# power_on.net
KiCad netlist of a schematic drawn in Altium Designer
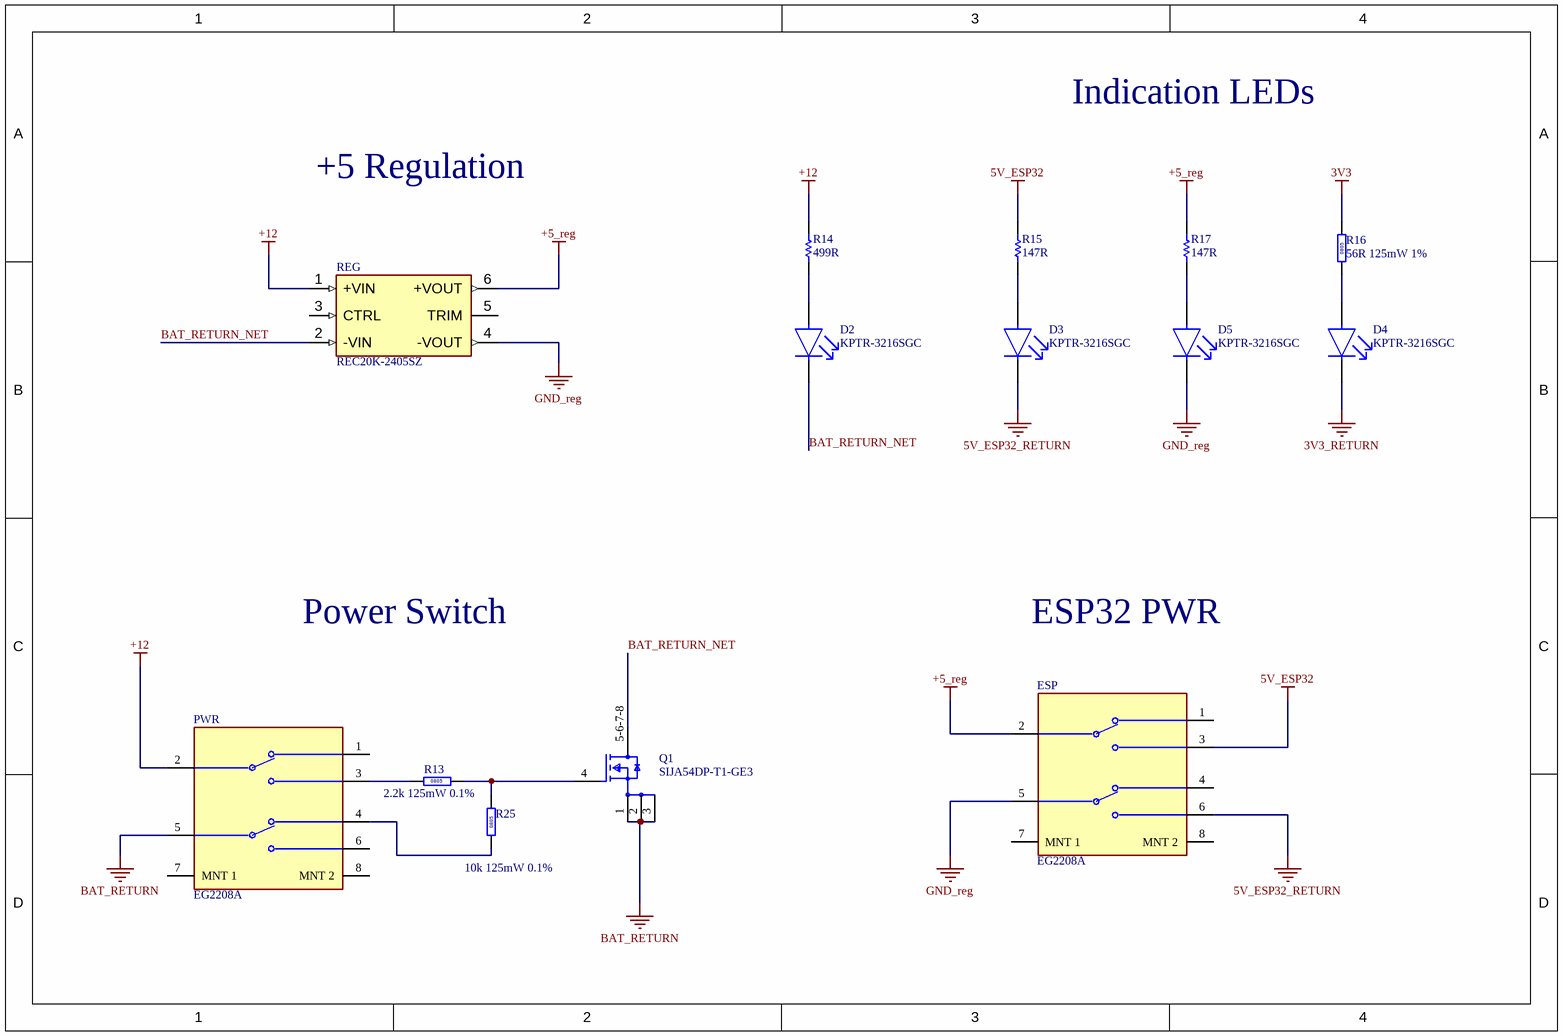
[diagram p0: power_on.SchDoc]

(export (version "E")
  (design (tool "Eeschema 10.0.6"))
  (components
    (comp (ref "D2")
      (value "KPTR-3216SGC")
      (footprint "KPTR-3216SGC-Footprint-1")
      (description "Single Color LED, Super Bright Green, Water Clear, 1.6mm")
      (fields (field (name "MANUFACTURER") "Kingbright"))
      (libsource (lib "Andor Technology") (part "KPTR-3216SGC-Symbol-1"))
    )
    (comp (ref "D3")
      (value "KPTR-3216SGC")
      (footprint "KPTR-3216SGC-Footprint-1")
      (description "Single Color LED, Super Bright Green, Water Clear, 1.6mm")
      (fields (field (name "MANUFACTURER") "Kingbright"))
      (libsource (lib "Andor Technology") (part "KPTR-3216SGC-Symbol-1"))
    )
    (comp (ref "D4")
      (value "KPTR-3216SGC")
      (footprint "KPTR-3216SGC-Footprint-1")
      (description "Single Color LED, Super Bright Green, Water Clear, 1.6mm")
      (fields (field (name "MANUFACTURER") "Kingbright"))
      (libsource (lib "Andor Technology") (part "KPTR-3216SGC-Symbol-1"))
    )
    (comp (ref "D5")
      (value "KPTR-3216SGC")
      (footprint "KPTR-3216SGC-Footprint-1")
      (description "Single Color LED, Super Bright Green, Water Clear, 1.6mm")
      (fields (field (name "MANUFACTURER") "Kingbright"))
      (libsource (lib "Andor Technology") (part "KPTR-3216SGC-Symbol-1"))
    )
    (comp (ref "ESP")
      (value "EG2208A")
      (footprint "FP-EG2208A-MFG")
      (description "SWITCH SLIDE DPDT 200MA 30V")
      (libsource (lib "Altium Content Vault") (part "285c6a36e34860615e93578c1884609"))
    )
    (comp (ref "PWR")
      (value "EG2208A")
      (footprint "FP-EG2208A-MFG")
      (description "SWITCH SLIDE DPDT 200MA 30V")
      (libsource (lib "Altium Content Vault") (part "285c6a36e34860615e93578c1884609"))
    )
    (comp (ref "Q1")
      (value "SIJA54DP-T1-GE3")
      (footprint "SIJA54DP-T1-GE3-Footprint-2")
      (description "Transistor, SMD, MOSFET, N-Chan, 40V")
      (fields (field (name "MANUFACTURER") "Vishay"))
      (libsource (lib "Andor Technology") (part "SIJA54DP-T1-GE3-Symbol-1"))
    )
    (comp (ref "R13")
      (value "2.2k 125mW 0.1%")
      (footprint "RESC2013X60X35ML10T20")
      (description "Res, SMD, 100k, 125mW, 0.1%, ±25ppm, 0805")
      (fields (field (name "MANUFACTURER") "Panasonic") (field (name "TOLERANCE") "0.1%"))
      (libsource (lib "") (part "Resistor_0805_1"))
    )
    (comp (ref "R14")
      (value "499R")
      (footprint "RESC2013X60X40ML20T25")
      (fields (field (name "PART NUMBER") "ERA6AEB4990V") (field (name "MANUFACTURER") "Panasonic"))
      (libsource (lib "Altium Content Vault") (part "RES"))
    )
    (comp (ref "R15")
      (value "147R")
      (footprint "RESC2013X60X40ML20T25")
      (fields (field (name "PART NUMBER") "ERA6AEB4990V") (field (name "MANUFACTURER") "Panasonic"))
      (libsource (lib "Altium Content Vault") (part "RES"))
    )
    (comp (ref "R16")
      (value "56R 125mW 1%")
      (footprint "RESC2013X60X35ML10T20")
      (description "Res, SMD, 56R, 125mW, 1%, ±100ppm, 0805")
      (fields (field (name "MANUFACTURER") "Panasonic") (field (name "TOLERANCE") "1%"))
      (libsource (lib "Andor Technology") (part "Resistor_0805"))
    )
    (comp (ref "R17")
      (value "147R")
      (footprint "RESC2013X60X40ML20T25")
      (fields (field (name "PART NUMBER") "ERA6AEB4990V") (field (name "MANUFACTURER") "Panasonic"))
      (libsource (lib "Altium Content Vault") (part "RES"))
    )
    (comp (ref "R25")
      (value "10k 125mW 0.1%")
      (footprint "RESC2013X60X35ML10T20")
      (description "Res, SMD, 100k, 125mW, 0.1%, ±25ppm, 0805")
      (fields (field (name "MANUFACTURER") "Panasonic") (field (name "TOLERANCE") "0.1%"))
      (libsource (lib "Andor Technology") (part "Resistor_0805"))
    )
    (comp (ref "REG")
      (value "REC20K-2405SZ")
      (footprint "CONV_REC20K-2405SZ")
      (fields (field (name "MF") "Recom Power"))
      (libsource (lib "REC20K-2405SZ") (part "REC20K-2405SZ"))
    )
  )
  (nets
    (net (code "1") (name "+5_reg") (class "Default")
      (node (ref "ESP") (pin "2") (pinfunction "Com_2") (pintype "passive"))
      (node (ref "R17") (pin "2") (pinfunction "2_2") (pintype "passive"))
      (node (ref "REG") (pin "6") (pinfunction "+VOUT_6") (pintype "output"))
    )
    (net (code "2") (name "+12") (class "Default")
      (node (ref "PWR") (pin "2") (pinfunction "Com_2") (pintype "passive"))
      (node (ref "R14") (pin "2") (pinfunction "2_2") (pintype "passive"))
      (node (ref "REG") (pin "1") (pinfunction "+VIN_1") (pintype "input"))
    )
    (net (code "3") (name "/BAT_RETURN_NET") (class "Default")
      (node (ref "D2") (pin "2") (pinfunction "C_2") (pintype "passive"))
      (node (ref "Q1") (pin "5-6-7-8") (pinfunction "D_5-6-7-8") (pintype "passive"))
      (node (ref "REG") (pin "2") (pinfunction "-VIN_2") (pintype "input"))
    )
    (net (code "4") (name "3V3") (class "Default")
      (node (ref "R16") (pin "2") (pinfunction "2_2") (pintype "passive"))
    )
    (net (code "5") (name "3V3_RETURN") (class "Default")
      (node (ref "D4") (pin "2") (pinfunction "C_2") (pintype "passive"))
    )
    (net (code "6") (name "5V_ESP32") (class "Default")
      (node (ref "ESP") (pin "3") (pinfunction "3_3") (pintype "passive"))
      (node (ref "R15") (pin "2") (pinfunction "2_2") (pintype "passive"))
    )
    (net (code "7") (name "5V_ESP32_RETURN") (class "Default")
      (node (ref "D3") (pin "2") (pinfunction "C_2") (pintype "passive"))
      (node (ref "ESP") (pin "6") (pinfunction "6_6") (pintype "passive"))
    )
    (net (code "8") (name "BAT_RETURN") (class "Default")
      (node (ref "PWR") (pin "5") (pinfunction "Com_5") (pintype "passive"))
      (node (ref "Q1") (pin "1") (pinfunction "S_1") (pintype "passive"))
      (node (ref "Q1") (pin "2") (pinfunction "S_2") (pintype "passive"))
      (node (ref "Q1") (pin "3") (pinfunction "S_3") (pintype "passive"))
    )
    (net (code "9") (name "GND_reg") (class "Default")
      (node (ref "D5") (pin "2") (pinfunction "C_2") (pintype "passive"))
      (node (ref "ESP") (pin "5") (pinfunction "Com_5") (pintype "passive"))
      (node (ref "REG") (pin "4") (pinfunction "-VOUT_4") (pintype "output"))
    )
    (net (code "10") (name "Net-(D2-A)") (class "Default")
      (node (ref "D2") (pin "1") (pinfunction "A_1") (pintype "passive"))
      (node (ref "R14") (pin "1") (pinfunction "1_1") (pintype "passive"))
    )
    (net (code "11") (name "Net-(D3-A)") (class "Default")
      (node (ref "D3") (pin "1") (pinfunction "A_1") (pintype "passive"))
      (node (ref "R15") (pin "1") (pinfunction "1_1") (pintype "passive"))
    )
    (net (code "12") (name "Net-(D4-A)") (class "Default")
      (node (ref "D4") (pin "1") (pinfunction "A_1") (pintype "passive"))
      (node (ref "R16") (pin "1") (pinfunction "1_1") (pintype "passive"))
    )
    (net (code "13") (name "Net-(D5-A)") (class "Default")
      (node (ref "D5") (pin "1") (pinfunction "A_1") (pintype "passive"))
      (node (ref "R17") (pin "1") (pinfunction "1_1") (pintype "passive"))
    )
    (net (code "14") (name "Net-(PWR-Pad3)") (class "Default")
      (node (ref "PWR") (pin "3") (pinfunction "3_3") (pintype "passive"))
      (node (ref "R13") (pin "1") (pinfunction "1_1") (pintype "passive"))
    )
    (net (code "15") (name "Net-(PWR-Pad4)") (class "Default")
      (node (ref "PWR") (pin "4") (pinfunction "4_4") (pintype "passive"))
      (node (ref "R25") (pin "1") (pinfunction "1_1") (pintype "passive"))
    )
    (net (code "16") (name "Net-(Q1-G)") (class "Default")
      (node (ref "Q1") (pin "4") (pinfunction "G_4") (pintype "passive"))
      (node (ref "R13") (pin "2") (pinfunction "2_2") (pintype "passive"))
      (node (ref "R25") (pin "2") (pinfunction "2_2") (pintype "passive"))
    )
    (net (code "17") (name "unconnected-(ESP-MNT_1-Pad7)") (class "Default")
      (node (ref "ESP") (pin "7") (pinfunction "MNT_1_7") (pintype "passive"))
    )
    (net (code "18") (name "unconnected-(ESP-MNT_2-Pad8)") (class "Default")
      (node (ref "ESP") (pin "8") (pinfunction "MNT_2_8") (pintype "passive"))
    )
    (net (code "19") (name "unconnected-(ESP-Pad1)") (class "Default")
      (node (ref "ESP") (pin "1") (pinfunction "1_1") (pintype "passive"))
    )
    (net (code "20") (name "unconnected-(ESP-Pad4)") (class "Default")
      (node (ref "ESP") (pin "4") (pinfunction "4_4") (pintype "passive"))
    )
    (net (code "21") (name "unconnected-(PWR-MNT_1-Pad7)") (class "Default")
      (node (ref "PWR") (pin "7") (pinfunction "MNT_1_7") (pintype "passive"))
    )
    (net (code "22") (name "unconnected-(PWR-MNT_2-Pad8)") (class "Default")
      (node (ref "PWR") (pin "8") (pinfunction "MNT_2_8") (pintype "passive"))
    )
    (net (code "23") (name "unconnected-(PWR-Pad1)") (class "Default")
      (node (ref "PWR") (pin "1") (pinfunction "1_1") (pintype "passive"))
    )
    (net (code "24") (name "unconnected-(PWR-Pad6)") (class "Default")
      (node (ref "PWR") (pin "6") (pinfunction "6_6") (pintype "passive"))
    )
    (net (code "25") (name "unconnected-(REG-CTRL-Pad3)") (class "Default")
      (node (ref "REG") (pin "3") (pinfunction "CTRL_3") (pintype "input"))
    )
    (net (code "26") (name "unconnected-(REG-TRIM-Pad5)") (class "Default")
      (node (ref "REG") (pin "5") (pinfunction "TRIM_5") (pintype "passive"))
    )
  )
)
